# robot-arm.net
KiCad netlist of a schematic drawn in Altium Designer
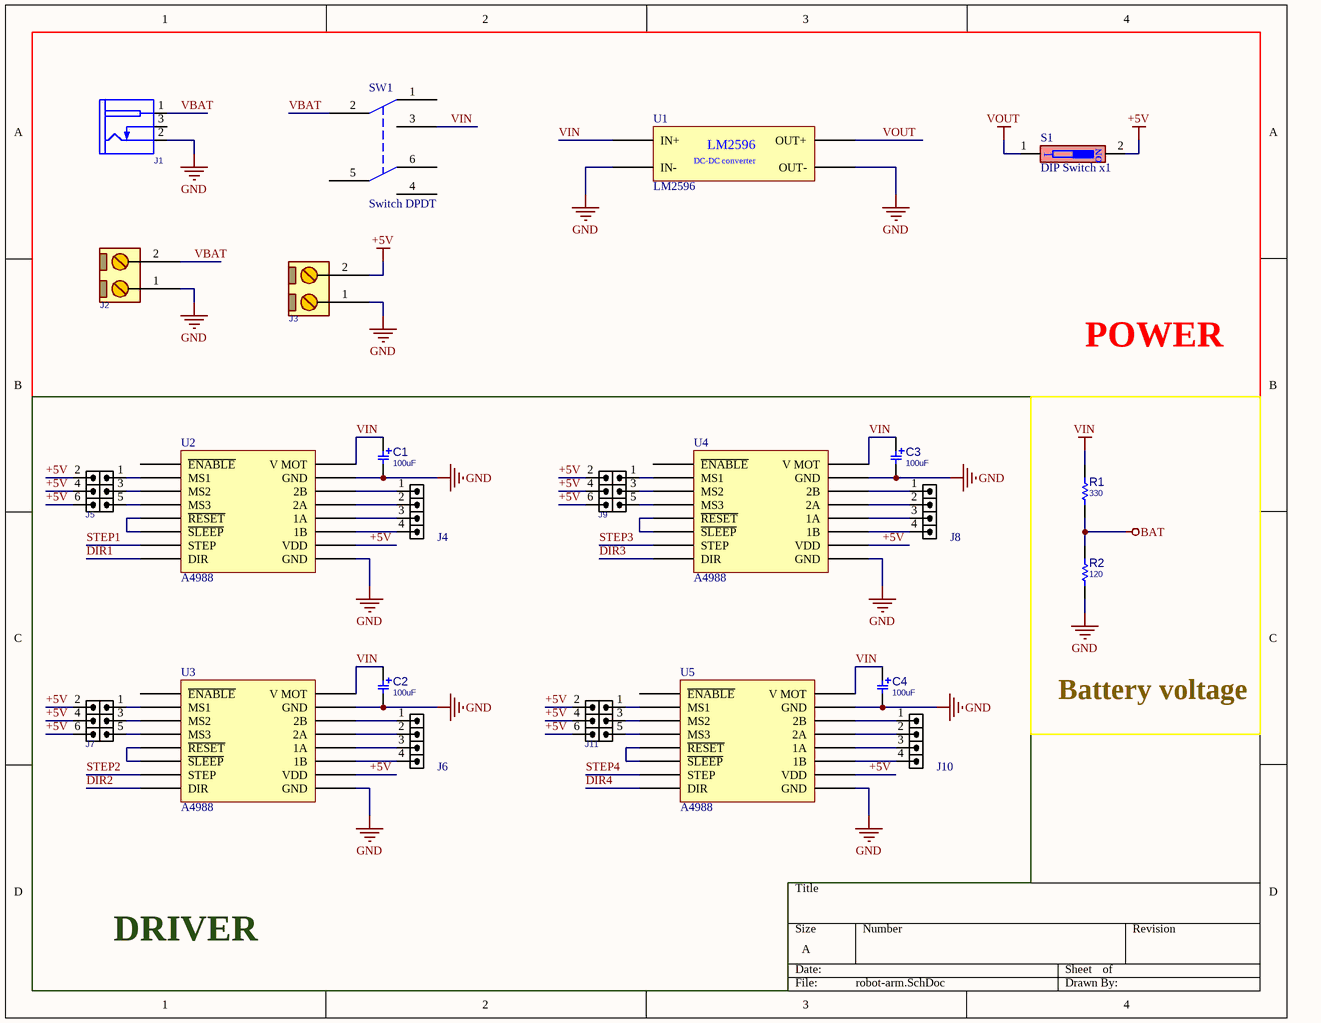
[diagram p0: robot-arm.SchDoc]

(export (version "E")
  (design (tool "Eeschema 10.0.6"))
  (components
    (comp (ref "C1")
      (value "100uF")
      (footprint "C_EL_6X11")
      (description "CAP, THD, ELEC,")
      (fields (field (name "MANF_P#") "MANF_PART#") (field (name "MANF") "MANF"))
      (libsource (lib "PASSIVE") (part "CAP_THD_EL"))
    )
    (comp (ref "C2")
      (value "100uF")
      (footprint "C_EL_6X11")
      (description "CAP, THD, ELEC,")
      (fields (field (name "MANF_P#") "MANF_PART#") (field (name "MANF") "MANF"))
      (libsource (lib "PASSIVE") (part "CAP_THD_EL"))
    )
    (comp (ref "C3")
      (value "100uF")
      (footprint "C_EL_6X11")
      (description "CAP, THD, ELEC,")
      (fields (field (name "MANF_P#") "MANF_PART#") (field (name "MANF") "MANF"))
      (libsource (lib "PASSIVE") (part "CAP_THD_EL"))
    )
    (comp (ref "C4")
      (value "100uF")
      (footprint "C_EL_6X11")
      (description "CAP, THD, ELEC,")
      (fields (field (name "MANF_P#") "MANF_PART#") (field (name "MANF") "MANF"))
      (libsource (lib "PASSIVE") (part "CAP_THD_EL"))
    )
    (comp (ref "J1")
      (value "DC_POWER_JACK")
      (footprint "JAC_PWR2MM")
      (description "CONN, PWR JACK DC, PLUG DIAM 2.0MM RA THD")
      (fields
        (field (name "MANF") "CUI STACK")
        (field (name "MANF_P#") "PJ-202A, PJ-002AH, PJ-102AH, KLDX-0202")
      )
      (libsource (lib "Connector_PWR") (part "CONN_PWR_JACK2MM"))
    )
    (comp (ref "J2")
      (value "CONN_TB2")
      (footprint "TBB_2")
      (description "CONN, TERMINAL BLOCK, 5.08mm pitch")
      (libsource (lib "Connector_PWR") (part "CONN_TB2"))
    )
    (comp (ref "J3")
      (value "CONN_TB2")
      (footprint "TBB_2")
      (description "CONN, TERMINAL BLOCK, 5.08mm pitch")
      (libsource (lib "Connector_PWR") (part "CONN_TB2"))
    )
    (comp (ref "J4")
      (value "HDR1X4")
      (footprint "HDR_M_1X4")
      (description "CONN, HEADER, Male, pitch: 2.54mm, 4POS")
      (libsource (lib "Connector_HDR") (part "HDR_M_1X4"))
    )
    (comp (ref "J5")
      (value "HDRM_2X3")
      (footprint "HDR_M_2X3")
      (description "CONN, HEADER, Male, pitch: 2.54mm, 6POS")
      (fields (field (name "MANF_P#") "MANF_PART#") (field (name "MANF") "MANF"))
      (libsource (lib "Connector_HDR") (part "HDR_M_2X3"))
    )
    (comp (ref "J6")
      (value "HDR1X4")
      (footprint "HDR_M_1X4")
      (description "CONN, HEADER, Male, pitch: 2.54mm, 4POS")
      (libsource (lib "Connector_HDR") (part "HDR_M_1X4"))
    )
    (comp (ref "J7")
      (value "HDRM_2X3")
      (footprint "HDR_M_2X3")
      (description "CONN, HEADER, Male, pitch: 2.54mm, 6POS")
      (fields (field (name "MANF_P#") "MANF_PART#") (field (name "MANF") "MANF"))
      (libsource (lib "Connector_HDR") (part "HDR_M_2X3"))
    )
    (comp (ref "J8")
      (value "HDR1X4")
      (footprint "HDR_M_1X4")
      (description "CONN, HEADER, Male, pitch: 2.54mm, 4POS")
      (libsource (lib "Connector_HDR") (part "HDR_M_1X4"))
    )
    (comp (ref "J9")
      (value "HDRM_2X3")
      (footprint "HDR_M_2X3")
      (description "CONN, HEADER, Male, pitch: 2.54mm, 6POS")
      (fields (field (name "MANF_P#") "MANF_PART#") (field (name "MANF") "MANF"))
      (libsource (lib "Connector_HDR") (part "HDR_M_2X3"))
    )
    (comp (ref "J10")
      (value "HDR1X4")
      (footprint "HDR_M_1X4")
      (description "CONN, HEADER, Male, pitch: 2.54mm, 4POS")
      (libsource (lib "Connector_HDR") (part "HDR_M_1X4"))
    )
    (comp (ref "J11")
      (value "HDRM_2X3")
      (footprint "HDR_M_2X3")
      (description "CONN, HEADER, Male, pitch: 2.54mm, 6POS")
      (fields (field (name "MANF_P#") "MANF_PART#") (field (name "MANF") "MANF"))
      (libsource (lib "Connector_HDR") (part "HDR_M_2X3"))
    )
    (comp (ref "R1")
      (value "330")
      (footprint "R025W_AX04")
      (description "RESISTOR, THD")
      (fields (field (name "MANF_P#") "RK73H1ETTP4701F") (field (name "MANF") "KOA SPEER"))
      (libsource (lib "PASSIVE") (part "RES_THD"))
    )
    (comp (ref "R2")
      (value "120")
      (footprint "R025W_AX04")
      (description "RESISTOR, THD")
      (fields (field (name "MANF_P#") "RK73H1ETTP4701F") (field (name "MANF") "KOA SPEER"))
      (libsource (lib "PASSIVE") (part "RES_THD"))
    )
    (comp (ref "S1")
      (value "DIP Switch x1")
      (footprint "DIP Switch x1")
      (libsource (lib "switch6pin") (part "DIP Switch x1"))
    )
    (comp (ref "SW1")
      (value "Switch DPDT")
      (footprint "Switch DPDT")
      (libsource (lib "switch6pin") (part "Switch DPDT"))
    )
    (comp (ref "U1")
      (value "LM2596")
      (footprint "LM2596_MODULE")
      (description "DC-DC converter")
      (libsource (lib "Module") (part "LM2596_ADJ"))
    )
    (comp (ref "U2")
      (value "A4988")
      (footprint "DRIVER MOTOR_A4988")
      (description "Driver stepper motor")
      (libsource (lib "Module") (part "A4988"))
    )
    (comp (ref "U3")
      (value "A4988")
      (footprint "DRIVER MOTOR_A4988")
      (description "Driver stepper motor")
      (libsource (lib "Module") (part "A4988"))
    )
    (comp (ref "U4")
      (value "A4988")
      (footprint "DRIVER MOTOR_A4988")
      (description "Driver stepper motor")
      (libsource (lib "Module") (part "A4988"))
    )
    (comp (ref "U5")
      (value "A4988")
      (footprint "DRIVER MOTOR_A4988")
      (description "Driver stepper motor")
      (libsource (lib "Module") (part "A4988"))
    )
  )
  (nets
    (net (code "1") (name "+5V") (class "Default")
      (node (ref "J11") (pin "2") (pinfunction "2_2") (pintype "passive"))
      (node (ref "J11") (pin "4") (pinfunction "4_4") (pintype "passive"))
      (node (ref "J11") (pin "6") (pinfunction "6_6") (pintype "passive"))
      (node (ref "J3") (pin "2") (pinfunction "2_2") (pintype "passive"))
      (node (ref "J5") (pin "2") (pinfunction "2_2") (pintype "passive"))
      (node (ref "J5") (pin "4") (pinfunction "4_4") (pintype "passive"))
      (node (ref "J5") (pin "6") (pinfunction "6_6") (pintype "passive"))
      (node (ref "J7") (pin "2") (pinfunction "2_2") (pintype "passive"))
      (node (ref "J7") (pin "4") (pinfunction "4_4") (pintype "passive"))
      (node (ref "J7") (pin "6") (pinfunction "6_6") (pintype "passive"))
      (node (ref "J9") (pin "2") (pinfunction "2_2") (pintype "passive"))
      (node (ref "J9") (pin "4") (pinfunction "4_4") (pintype "passive"))
      (node (ref "J9") (pin "6") (pinfunction "6_6") (pintype "passive"))
      (node (ref "S1") (pin "2") (pinfunction "2_2") (pintype "passive"))
      (node (ref "U2") (pin "10") (pinfunction "VDD_10") (pintype "passive"))
      (node (ref "U3") (pin "10") (pinfunction "VDD_10") (pintype "passive"))
      (node (ref "U4") (pin "10") (pinfunction "VDD_10") (pintype "passive"))
      (node (ref "U5") (pin "10") (pinfunction "VDD_10") (pintype "passive"))
    )
    (net (code "2") (name "/DIR1") (class "Default")
      (node (ref "U2") (pin "8") (pinfunction "DIR_8") (pintype "passive"))
    )
    (net (code "3") (name "/DIR2") (class "Default")
      (node (ref "U3") (pin "8") (pinfunction "DIR_8") (pintype "passive"))
    )
    (net (code "4") (name "/DIR3") (class "Default")
      (node (ref "U4") (pin "8") (pinfunction "DIR_8") (pintype "passive"))
    )
    (net (code "5") (name "/DIR4") (class "Default")
      (node (ref "U5") (pin "8") (pinfunction "DIR_8") (pintype "passive"))
    )
    (net (code "6") (name "/STEP1") (class "Default")
      (node (ref "U2") (pin "7") (pinfunction "STEP_7") (pintype "passive"))
    )
    (net (code "7") (name "/STEP2") (class "Default")
      (node (ref "U3") (pin "7") (pinfunction "STEP_7") (pintype "passive"))
    )
    (net (code "8") (name "/STEP3") (class "Default")
      (node (ref "U4") (pin "7") (pinfunction "STEP_7") (pintype "passive"))
    )
    (net (code "9") (name "/STEP4") (class "Default")
      (node (ref "U5") (pin "7") (pinfunction "STEP_7") (pintype "passive"))
    )
    (net (code "10") (name "/VBAT") (class "Default")
      (node (ref "J1") (pin "1") (pinfunction "TIP_1") (pintype "power_in"))
      (node (ref "J2") (pin "2") (pinfunction "2_2") (pintype "passive"))
      (node (ref "SW1") (pin "2") (pinfunction "2_2") (pintype "passive"))
    )
    (net (code "11") (name "BAT") (class "Default")
      (node (ref "R1") (pin "1") (pinfunction "1_1") (pintype "passive"))
      (node (ref "R2") (pin "2") (pinfunction "2_2") (pintype "passive"))
    )
    (net (code "12") (name "GND") (class "Default")
      (node (ref "C1") (pin "2") (pinfunction "2_2") (pintype "passive"))
      (node (ref "C2") (pin "2") (pinfunction "2_2") (pintype "passive"))
      (node (ref "C3") (pin "2") (pinfunction "2_2") (pintype "passive"))
      (node (ref "C4") (pin "2") (pinfunction "2_2") (pintype "passive"))
      (node (ref "J1") (pin "2") (pinfunction "SLEEVE_2") (pintype "power_in"))
      (node (ref "J2") (pin "1") (pinfunction "1_1") (pintype "passive"))
      (node (ref "J3") (pin "1") (pinfunction "1_1") (pintype "passive"))
      (node (ref "R2") (pin "1") (pinfunction "1_1") (pintype "passive"))
      (node (ref "U1") (pin "2") (pinfunction "IN-_2") (pintype "passive"))
      (node (ref "U1") (pin "3") (pinfunction "OUT-_3") (pintype "passive"))
      (node (ref "U2") (pin "15") (pinfunction "GND_15") (pintype "passive"))
      (node (ref "U2") (pin "9") (pinfunction "GND_9") (pintype "passive"))
      (node (ref "U3") (pin "15") (pinfunction "GND_15") (pintype "passive"))
      (node (ref "U3") (pin "9") (pinfunction "GND_9") (pintype "passive"))
      (node (ref "U4") (pin "15") (pinfunction "GND_15") (pintype "passive"))
      (node (ref "U4") (pin "9") (pinfunction "GND_9") (pintype "passive"))
      (node (ref "U5") (pin "15") (pinfunction "GND_15") (pintype "passive"))
      (node (ref "U5") (pin "9") (pinfunction "GND_9") (pintype "passive"))
    )
    (net (code "13") (name "Net-(U2-1A)") (class "Default")
      (node (ref "J4") (pin "3") (pinfunction "3_3") (pintype "passive"))
      (node (ref "U2") (pin "12") (pinfunction "1A_12") (pintype "passive"))
    )
    (net (code "14") (name "Net-(U2-1B)") (class "Default")
      (node (ref "J4") (pin "4") (pinfunction "4_4") (pintype "passive"))
      (node (ref "U2") (pin "11") (pinfunction "1B_11") (pintype "passive"))
    )
    (net (code "15") (name "Net-(U2-2A)") (class "Default")
      (node (ref "J4") (pin "2") (pinfunction "2_2") (pintype "passive"))
      (node (ref "U2") (pin "13") (pinfunction "2A_13") (pintype "passive"))
    )
    (net (code "16") (name "Net-(U2-2B)") (class "Default")
      (node (ref "J4") (pin "1") (pinfunction "1_1") (pintype "passive"))
      (node (ref "U2") (pin "14") (pinfunction "2B_14") (pintype "passive"))
    )
    (net (code "17") (name "Net-(U2-MS1)") (class "Default")
      (node (ref "J5") (pin "1") (pinfunction "1_1") (pintype "passive"))
      (node (ref "U2") (pin "2") (pinfunction "MS1_2") (pintype "passive"))
    )
    (net (code "18") (name "Net-(U2-MS2)") (class "Default")
      (node (ref "J5") (pin "3") (pinfunction "3_3") (pintype "passive"))
      (node (ref "U2") (pin "3") (pinfunction "MS2_3") (pintype "passive"))
    )
    (net (code "19") (name "Net-(U2-MS3)") (class "Default")
      (node (ref "J5") (pin "5") (pinfunction "5_5") (pintype "passive"))
      (node (ref "U2") (pin "4") (pinfunction "MS3_4") (pintype "passive"))
    )
    (net (code "20") (name "Net-(U2-~{RESET})") (class "Default")
      (node (ref "U2") (pin "5") (pinfunction "~{RESET}_5") (pintype "passive"))
      (node (ref "U2") (pin "6") (pinfunction "~{SLEEP}_6") (pintype "passive"))
    )
    (net (code "21") (name "Net-(U3-1A)") (class "Default")
      (node (ref "J6") (pin "3") (pinfunction "3_3") (pintype "passive"))
      (node (ref "U3") (pin "12") (pinfunction "1A_12") (pintype "passive"))
    )
    (net (code "22") (name "Net-(U3-1B)") (class "Default")
      (node (ref "J6") (pin "4") (pinfunction "4_4") (pintype "passive"))
      (node (ref "U3") (pin "11") (pinfunction "1B_11") (pintype "passive"))
    )
    (net (code "23") (name "Net-(U3-2A)") (class "Default")
      (node (ref "J6") (pin "2") (pinfunction "2_2") (pintype "passive"))
      (node (ref "U3") (pin "13") (pinfunction "2A_13") (pintype "passive"))
    )
    (net (code "24") (name "Net-(U3-2B)") (class "Default")
      (node (ref "J6") (pin "1") (pinfunction "1_1") (pintype "passive"))
      (node (ref "U3") (pin "14") (pinfunction "2B_14") (pintype "passive"))
    )
    (net (code "25") (name "Net-(U3-MS1)") (class "Default")
      (node (ref "J7") (pin "1") (pinfunction "1_1") (pintype "passive"))
      (node (ref "U3") (pin "2") (pinfunction "MS1_2") (pintype "passive"))
    )
    (net (code "26") (name "Net-(U3-MS2)") (class "Default")
      (node (ref "J7") (pin "3") (pinfunction "3_3") (pintype "passive"))
      (node (ref "U3") (pin "3") (pinfunction "MS2_3") (pintype "passive"))
    )
    (net (code "27") (name "Net-(U3-MS3)") (class "Default")
      (node (ref "J7") (pin "5") (pinfunction "5_5") (pintype "passive"))
      (node (ref "U3") (pin "4") (pinfunction "MS3_4") (pintype "passive"))
    )
    (net (code "28") (name "Net-(U3-~{RESET})") (class "Default")
      (node (ref "U3") (pin "5") (pinfunction "~{RESET}_5") (pintype "passive"))
      (node (ref "U3") (pin "6") (pinfunction "~{SLEEP}_6") (pintype "passive"))
    )
    (net (code "29") (name "Net-(U4-1A)") (class "Default")
      (node (ref "J8") (pin "3") (pinfunction "3_3") (pintype "passive"))
      (node (ref "U4") (pin "12") (pinfunction "1A_12") (pintype "passive"))
    )
    (net (code "30") (name "Net-(U4-1B)") (class "Default")
      (node (ref "J8") (pin "4") (pinfunction "4_4") (pintype "passive"))
      (node (ref "U4") (pin "11") (pinfunction "1B_11") (pintype "passive"))
    )
    (net (code "31") (name "Net-(U4-2A)") (class "Default")
      (node (ref "J8") (pin "2") (pinfunction "2_2") (pintype "passive"))
      (node (ref "U4") (pin "13") (pinfunction "2A_13") (pintype "passive"))
    )
    (net (code "32") (name "Net-(U4-2B)") (class "Default")
      (node (ref "J8") (pin "1") (pinfunction "1_1") (pintype "passive"))
      (node (ref "U4") (pin "14") (pinfunction "2B_14") (pintype "passive"))
    )
    (net (code "33") (name "Net-(U4-MS1)") (class "Default")
      (node (ref "J9") (pin "1") (pinfunction "1_1") (pintype "passive"))
      (node (ref "U4") (pin "2") (pinfunction "MS1_2") (pintype "passive"))
    )
    (net (code "34") (name "Net-(U4-MS2)") (class "Default")
      (node (ref "J9") (pin "3") (pinfunction "3_3") (pintype "passive"))
      (node (ref "U4") (pin "3") (pinfunction "MS2_3") (pintype "passive"))
    )
    (net (code "35") (name "Net-(U4-MS3)") (class "Default")
      (node (ref "J9") (pin "5") (pinfunction "5_5") (pintype "passive"))
      (node (ref "U4") (pin "4") (pinfunction "MS3_4") (pintype "passive"))
    )
    (net (code "36") (name "Net-(U4-~{RESET})") (class "Default")
      (node (ref "U4") (pin "5") (pinfunction "~{RESET}_5") (pintype "passive"))
      (node (ref "U4") (pin "6") (pinfunction "~{SLEEP}_6") (pintype "passive"))
    )
    (net (code "37") (name "Net-(U5-1A)") (class "Default")
      (node (ref "J10") (pin "3") (pinfunction "3_3") (pintype "passive"))
      (node (ref "U5") (pin "12") (pinfunction "1A_12") (pintype "passive"))
    )
    (net (code "38") (name "Net-(U5-1B)") (class "Default")
      (node (ref "J10") (pin "4") (pinfunction "4_4") (pintype "passive"))
      (node (ref "U5") (pin "11") (pinfunction "1B_11") (pintype "passive"))
    )
    (net (code "39") (name "Net-(U5-2A)") (class "Default")
      (node (ref "J10") (pin "2") (pinfunction "2_2") (pintype "passive"))
      (node (ref "U5") (pin "13") (pinfunction "2A_13") (pintype "passive"))
    )
    (net (code "40") (name "Net-(U5-2B)") (class "Default")
      (node (ref "J10") (pin "1") (pinfunction "1_1") (pintype "passive"))
      (node (ref "U5") (pin "14") (pinfunction "2B_14") (pintype "passive"))
    )
    (net (code "41") (name "Net-(U5-MS1)") (class "Default")
      (node (ref "J11") (pin "1") (pinfunction "1_1") (pintype "passive"))
      (node (ref "U5") (pin "2") (pinfunction "MS1_2") (pintype "passive"))
    )
    (net (code "42") (name "Net-(U5-MS2)") (class "Default")
      (node (ref "J11") (pin "3") (pinfunction "3_3") (pintype "passive"))
      (node (ref "U5") (pin "3") (pinfunction "MS2_3") (pintype "passive"))
    )
    (net (code "43") (name "Net-(U5-MS3)") (class "Default")
      (node (ref "J11") (pin "5") (pinfunction "5_5") (pintype "passive"))
      (node (ref "U5") (pin "4") (pinfunction "MS3_4") (pintype "passive"))
    )
    (net (code "44") (name "Net-(U5-~{RESET})") (class "Default")
      (node (ref "U5") (pin "5") (pinfunction "~{RESET}_5") (pintype "passive"))
      (node (ref "U5") (pin "6") (pinfunction "~{SLEEP}_6") (pintype "passive"))
    )
    (net (code "45") (name "VIN") (class "Default")
      (node (ref "C1") (pin "1") (pinfunction "1_1") (pintype "passive"))
      (node (ref "C2") (pin "1") (pinfunction "1_1") (pintype "passive"))
      (node (ref "C3") (pin "1") (pinfunction "1_1") (pintype "passive"))
      (node (ref "C4") (pin "1") (pinfunction "1_1") (pintype "passive"))
      (node (ref "R1") (pin "2") (pinfunction "2_2") (pintype "passive"))
      (node (ref "SW1") (pin "3") (pinfunction "3_3") (pintype "passive"))
      (node (ref "U1") (pin "1") (pinfunction "IN+_1") (pintype "passive"))
      (node (ref "U2") (pin "16") (pinfunction "V_MOT_16") (pintype "passive"))
      (node (ref "U3") (pin "16") (pinfunction "V_MOT_16") (pintype "passive"))
      (node (ref "U4") (pin "16") (pinfunction "V_MOT_16") (pintype "passive"))
      (node (ref "U5") (pin "16") (pinfunction "V_MOT_16") (pintype "passive"))
    )
    (net (code "46") (name "VOUT") (class "Default")
      (node (ref "S1") (pin "1") (pinfunction "1_1") (pintype "passive"))
      (node (ref "U1") (pin "4") (pinfunction "OUT+_4") (pintype "passive"))
    )
    (net (code "47") (name "unconnected-(J1-INSERTION_DET-Pad3)") (class "Default")
      (node (ref "J1") (pin "3") (pinfunction "INSERTION_DET_3") (pintype "power_in"))
    )
    (net (code "48") (name "unconnected-(SW1-Pad1)") (class "Default")
      (node (ref "SW1") (pin "1") (pinfunction "1_1") (pintype "passive"))
    )
    (net (code "49") (name "unconnected-(SW1-Pad4)") (class "Default")
      (node (ref "SW1") (pin "4") (pinfunction "4_4") (pintype "passive"))
    )
    (net (code "50") (name "unconnected-(SW1-Pad5)") (class "Default")
      (node (ref "SW1") (pin "5") (pinfunction "5_5") (pintype "passive"))
    )
    (net (code "51") (name "unconnected-(SW1-Pad6)") (class "Default")
      (node (ref "SW1") (pin "6") (pinfunction "6_6") (pintype "passive"))
    )
    (net (code "52") (name "unconnected-(U2-~{ENABLE}-Pad1)") (class "Default")
      (node (ref "U2") (pin "1") (pinfunction "~{ENABLE}_1") (pintype "passive"))
    )
    (net (code "53") (name "unconnected-(U3-~{ENABLE}-Pad1)") (class "Default")
      (node (ref "U3") (pin "1") (pinfunction "~{ENABLE}_1") (pintype "passive"))
    )
    (net (code "54") (name "unconnected-(U4-~{ENABLE}-Pad1)") (class "Default")
      (node (ref "U4") (pin "1") (pinfunction "~{ENABLE}_1") (pintype "passive"))
    )
    (net (code "55") (name "unconnected-(U5-~{ENABLE}-Pad1)") (class "Default")
      (node (ref "U5") (pin "1") (pinfunction "~{ENABLE}_1") (pintype "passive"))
    )
  )
)
